# Current_Sense.net
KiCad netlist of a schematic drawn in EAGLE
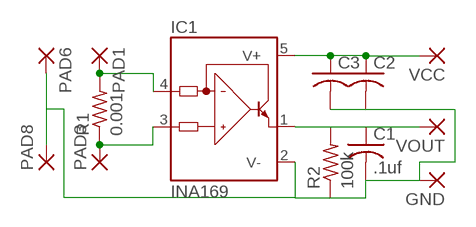
[diagram p0: schematic, sheet 1]

(export (version "E")
  (design (tool "Eeschema 10.0.6"))
  (components
    (comp (ref "C1")
      (value ".1uf")
      (footprint "eagle-import:C0805K")
      (libsource (lib "eagle-import") (part "C-USC0805K"))
    )
    (comp (ref "C2")
      (value "C-USC0805K")
      (footprint "eagle-import:C0805K")
      (libsource (lib "eagle-import") (part "C-USC0805K"))
    )
    (comp (ref "C3")
      (value "C-USC0805K")
      (footprint "eagle-import:C0805K")
      (libsource (lib "eagle-import") (part "C-USC0805K"))
    )
    (comp (ref "GND")
      (value "SMD2")
      (footprint "eagle-import:SMD1,27-2,54")
      (libsource (lib "eagle-import") (part "SMD2"))
    )
    (comp (ref "IC1")
      (value "INA169")
      (footprint "eagle-import:SOT23-5")
      (fields (field (name "MF") "TEXAS INSTRUMENTS") (field (name "MPN") "INA138NA/250"))
      (libsource (lib "eagle-import") (part "INA138"))
    )
    (comp (ref "PAD1")
      (value "SMD5")
      (footprint "eagle-import:SMD2,54-5,08")
      (libsource (lib "eagle-import") (part "SMD5"))
    )
    (comp (ref "PAD3")
      (value "SMD5")
      (footprint "eagle-import:SMD2,54-5,08")
      (libsource (lib "eagle-import") (part "SMD5"))
    )
    (comp (ref "PAD6")
      (value "SMD5")
      (footprint "eagle-import:SMD2,54-5,08")
      (libsource (lib "eagle-import") (part "SMD5"))
    )
    (comp (ref "PAD8")
      (value "SMD5")
      (footprint "eagle-import:SMD2,54-5,08")
      (libsource (lib "eagle-import") (part "SMD5"))
    )
    (comp (ref "R1")
      (value "0.001")
      (footprint "eagle-import:R2512")
      (libsource (lib "eagle-import") (part "R-US_R2512"))
    )
    (comp (ref "R2")
      (value "100k")
      (footprint "eagle-import:R0805")
      (libsource (lib "eagle-import") (part "R-US_R0805"))
    )
    (comp (ref "VCC")
      (value "SMD2")
      (footprint "eagle-import:SMD1,27-2,54")
      (libsource (lib "eagle-import") (part "SMD2"))
    )
    (comp (ref "VOUT")
      (value "SMD2")
      (footprint "eagle-import:SMD1,27-2,54")
      (libsource (lib "eagle-import") (part "SMD2"))
    )
  )
  (nets
    (net (code "1") (name "Net-(GND-P)") (class "Default")
      (node (ref "C1") (pin "2") (pinfunction "2_2") (pintype "passive"))
      (node (ref "C2") (pin "2") (pinfunction "2_2") (pintype "passive"))
      (node (ref "C3") (pin "2") (pinfunction "2_2") (pintype "passive"))
      (node (ref "GND") (pin "1") (pinfunction "P_1") (pintype "passive"))
      (node (ref "IC1") (pin "2") (pinfunction "V-_2") (pintype "power_in"))
      (node (ref "PAD6") (pin "1") (pinfunction "P_1") (pintype "passive"))
      (node (ref "PAD8") (pin "1") (pinfunction "P_1") (pintype "passive"))
      (node (ref "R2") (pin "1") (pinfunction "1_1") (pintype "passive"))
    )
    (net (code "2") (name "Net-(IC1-IN+)") (class "Default")
      (node (ref "IC1") (pin "3") (pinfunction "IN+_3") (pintype "input"))
      (node (ref "PAD3") (pin "1") (pinfunction "P_1") (pintype "passive"))
      (node (ref "R1") (pin "1") (pinfunction "1_1") (pintype "passive"))
    )
    (net (code "3") (name "Net-(IC1-IN-)") (class "Default")
      (node (ref "IC1") (pin "4") (pinfunction "IN-_4") (pintype "input"))
      (node (ref "PAD1") (pin "1") (pinfunction "P_1") (pintype "passive"))
      (node (ref "R1") (pin "2") (pinfunction "2_2") (pintype "passive"))
    )
    (net (code "4") (name "Net-(IC1-OUT)") (class "Default")
      (node (ref "C1") (pin "1") (pinfunction "1_1") (pintype "passive"))
      (node (ref "IC1") (pin "1") (pinfunction "OUT_1") (pintype "output"))
      (node (ref "R2") (pin "2") (pinfunction "2_2") (pintype "passive"))
      (node (ref "VOUT") (pin "1") (pinfunction "P_1") (pintype "passive"))
    )
    (net (code "5") (name "Net-(IC1-V+)") (class "Default")
      (node (ref "C2") (pin "1") (pinfunction "1_1") (pintype "passive"))
      (node (ref "C3") (pin "1") (pinfunction "1_1") (pintype "passive"))
      (node (ref "IC1") (pin "5") (pinfunction "V+_5") (pintype "power_in"))
      (node (ref "VCC") (pin "1") (pinfunction "P_1") (pintype "passive"))
    )
  )
)
